# Level_Sensor.net
KiCad netlist of a schematic drawn in Altium Designer
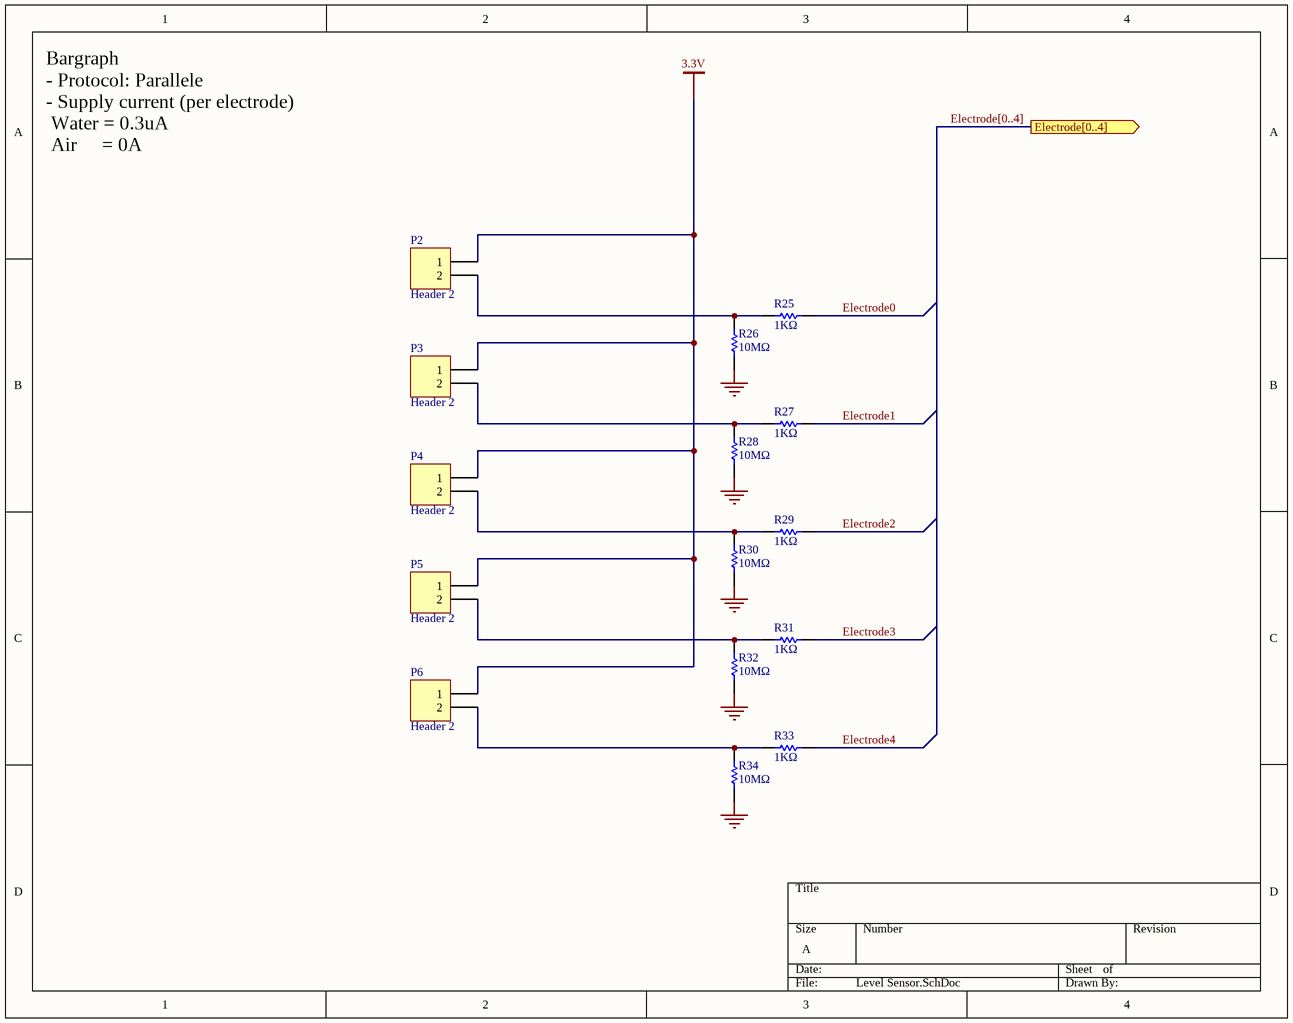
[diagram p0: Level Sensor.SchDoc]

(export (version "E")
  (design (tool "Eeschema 10.0.6"))
  (components
    (comp (ref "P2")
      (value "Header 2")
      (footprint "BORNIER")
      (description "Header, 2-Pin")
      (fields
        (field (name "MANUFACTURER") "BUCHANAN - TE CONNECTIVITY")
        (field (name "PUBLISHER") "Altium Limited")
      )
      (libsource (lib "Miscellaneous Connectors") (part "Header 2"))
    )
    (comp (ref "P3")
      (value "Header 2")
      (footprint "BORNIER")
      (description "Header, 2-Pin")
      (fields
        (field (name "MANUFACTURER") "BUCHANAN - TE CONNECTIVITY")
        (field (name "PUBLISHER") "Altium Limited")
      )
      (libsource (lib "Miscellaneous Connectors") (part "Header 2"))
    )
    (comp (ref "P4")
      (value "Header 2")
      (footprint "BORNIER")
      (description "Header, 2-Pin")
      (fields
        (field (name "MANUFACTURER") "BUCHANAN - TE CONNECTIVITY")
        (field (name "PUBLISHER") "Altium Limited")
      )
      (libsource (lib "Miscellaneous Connectors") (part "Header 2"))
    )
    (comp (ref "P5")
      (value "Header 2")
      (footprint "BORNIER")
      (description "Header, 2-Pin")
      (fields
        (field (name "MANUFACTURER") "BUCHANAN - TE CONNECTIVITY")
        (field (name "PUBLISHER") "Altium Limited")
      )
      (libsource (lib "Miscellaneous Connectors") (part "Header 2"))
    )
    (comp (ref "P6")
      (value "Header 2")
      (footprint "BORNIER")
      (description "Header, 2-Pin")
      (fields
        (field (name "MANUFACTURER") "BUCHANAN - TE CONNECTIVITY")
        (field (name "PUBLISHER") "Altium Limited")
      )
      (libsource (lib "Miscellaneous Connectors") (part "Header 2"))
    )
    (comp (ref "R25")
      (value "1KΩ")
      (footprint "R0603")
      (description "Resistor")
      (fields (field (name "MANUFACTURER") "MULTICOMP") (field (name "PUBLISHER") "Altium Limited"))
      (libsource (lib "Miscellaneous Devices") (part "Res1"))
    )
    (comp (ref "R26")
      (value "10MΩ")
      (footprint "R0603")
      (description "Resistor")
      (fields (field (name "MANUFACTURER") "MULTICOMP") (field (name "PUBLISHER") "Altium Limited"))
      (libsource (lib "Miscellaneous Devices") (part "Res1"))
    )
    (comp (ref "R27")
      (value "1KΩ")
      (footprint "R0603")
      (description "Resistor")
      (fields (field (name "MANUFACTURER") "MULTICOMP") (field (name "PUBLISHER") "Altium Limited"))
      (libsource (lib "Miscellaneous Devices") (part "Res1"))
    )
    (comp (ref "R28")
      (value "10MΩ")
      (footprint "R0603")
      (description "Resistor")
      (fields (field (name "MANUFACTURER") "MULTICOMP") (field (name "PUBLISHER") "Altium Limited"))
      (libsource (lib "Miscellaneous Devices") (part "Res1"))
    )
    (comp (ref "R29")
      (value "1KΩ")
      (footprint "R0603")
      (description "Resistor")
      (fields (field (name "MANUFACTURER") "MULTICOMP") (field (name "PUBLISHER") "Altium Limited"))
      (libsource (lib "Miscellaneous Devices") (part "Res1"))
    )
    (comp (ref "R30")
      (value "10MΩ")
      (footprint "R0603")
      (description "Resistor")
      (fields (field (name "MANUFACTURER") "MULTICOMP") (field (name "PUBLISHER") "Altium Limited"))
      (libsource (lib "Miscellaneous Devices") (part "Res1"))
    )
    (comp (ref "R31")
      (value "1KΩ")
      (footprint "R0603")
      (description "Resistor")
      (fields (field (name "MANUFACTURER") "MULTICOMP") (field (name "PUBLISHER") "Altium Limited"))
      (libsource (lib "Miscellaneous Devices") (part "Res1"))
    )
    (comp (ref "R32")
      (value "10MΩ")
      (footprint "R0603")
      (description "Resistor")
      (fields (field (name "MANUFACTURER") "MULTICOMP") (field (name "PUBLISHER") "Altium Limited"))
      (libsource (lib "Miscellaneous Devices") (part "Res1"))
    )
    (comp (ref "R33")
      (value "1KΩ")
      (footprint "R0603")
      (description "Resistor")
      (fields (field (name "MANUFACTURER") "MULTICOMP") (field (name "PUBLISHER") "Altium Limited"))
      (libsource (lib "Miscellaneous Devices") (part "Res1"))
    )
    (comp (ref "R34")
      (value "10MΩ")
      (footprint "R0603")
      (description "Resistor")
      (fields (field (name "MANUFACTURER") "MULTICOMP") (field (name "PUBLISHER") "Altium Limited"))
      (libsource (lib "Miscellaneous Devices") (part "Res1"))
    )
  )
  (nets
    (net (code "1") (name "/Electrode0") (class "Default")
      (node (ref "R25") (pin "2") (pinfunction "2_2") (pintype "passive"))
    )
    (net (code "2") (name "/Electrode1") (class "Default")
      (node (ref "R27") (pin "2") (pinfunction "2_2") (pintype "passive"))
    )
    (net (code "3") (name "/Electrode2") (class "Default")
      (node (ref "R29") (pin "2") (pinfunction "2_2") (pintype "passive"))
    )
    (net (code "4") (name "/Electrode3") (class "Default")
      (node (ref "R31") (pin "2") (pinfunction "2_2") (pintype "passive"))
    )
    (net (code "5") (name "/Electrode4") (class "Default")
      (node (ref "R33") (pin "2") (pinfunction "2_2") (pintype "passive"))
    )
    (net (code "7") (name "3.3V") (class "Default")
      (node (ref "P2") (pin "1") (pinfunction "1_1") (pintype "passive"))
      (node (ref "P3") (pin "1") (pinfunction "1_1") (pintype "passive"))
      (node (ref "P4") (pin "1") (pinfunction "1_1") (pintype "passive"))
      (node (ref "P5") (pin "1") (pinfunction "1_1") (pintype "passive"))
      (node (ref "P6") (pin "1") (pinfunction "1_1") (pintype "passive"))
    )
    (net (code "8") (name "GND") (class "Default")
      (node (ref "R26") (pin "1") (pinfunction "1_1") (pintype "passive"))
      (node (ref "R28") (pin "1") (pinfunction "1_1") (pintype "passive"))
      (node (ref "R30") (pin "1") (pinfunction "1_1") (pintype "passive"))
      (node (ref "R32") (pin "1") (pinfunction "1_1") (pintype "passive"))
      (node (ref "R34") (pin "1") (pinfunction "1_1") (pintype "passive"))
    )
    (net (code "9") (name "Net-(P2-Pad2)") (class "Default")
      (node (ref "P2") (pin "2") (pinfunction "2_2") (pintype "passive"))
      (node (ref "R25") (pin "1") (pinfunction "1_1") (pintype "passive"))
      (node (ref "R26") (pin "2") (pinfunction "2_2") (pintype "passive"))
    )
    (net (code "10") (name "Net-(P3-Pad2)") (class "Default")
      (node (ref "P3") (pin "2") (pinfunction "2_2") (pintype "passive"))
      (node (ref "R27") (pin "1") (pinfunction "1_1") (pintype "passive"))
      (node (ref "R28") (pin "2") (pinfunction "2_2") (pintype "passive"))
    )
    (net (code "11") (name "Net-(P4-Pad2)") (class "Default")
      (node (ref "P4") (pin "2") (pinfunction "2_2") (pintype "passive"))
      (node (ref "R29") (pin "1") (pinfunction "1_1") (pintype "passive"))
      (node (ref "R30") (pin "2") (pinfunction "2_2") (pintype "passive"))
    )
    (net (code "12") (name "Net-(P5-Pad2)") (class "Default")
      (node (ref "P5") (pin "2") (pinfunction "2_2") (pintype "passive"))
      (node (ref "R31") (pin "1") (pinfunction "1_1") (pintype "passive"))
      (node (ref "R32") (pin "2") (pinfunction "2_2") (pintype "passive"))
    )
    (net (code "13") (name "Net-(P6-Pad2)") (class "Default")
      (node (ref "P6") (pin "2") (pinfunction "2_2") (pintype "passive"))
      (node (ref "R33") (pin "1") (pinfunction "1_1") (pintype "passive"))
      (node (ref "R34") (pin "2") (pinfunction "2_2") (pintype "passive"))
    )
  )
)
